# PSDT_RAM_v1_0_0.net
KiCad netlist of a schematic drawn in Altium Designer
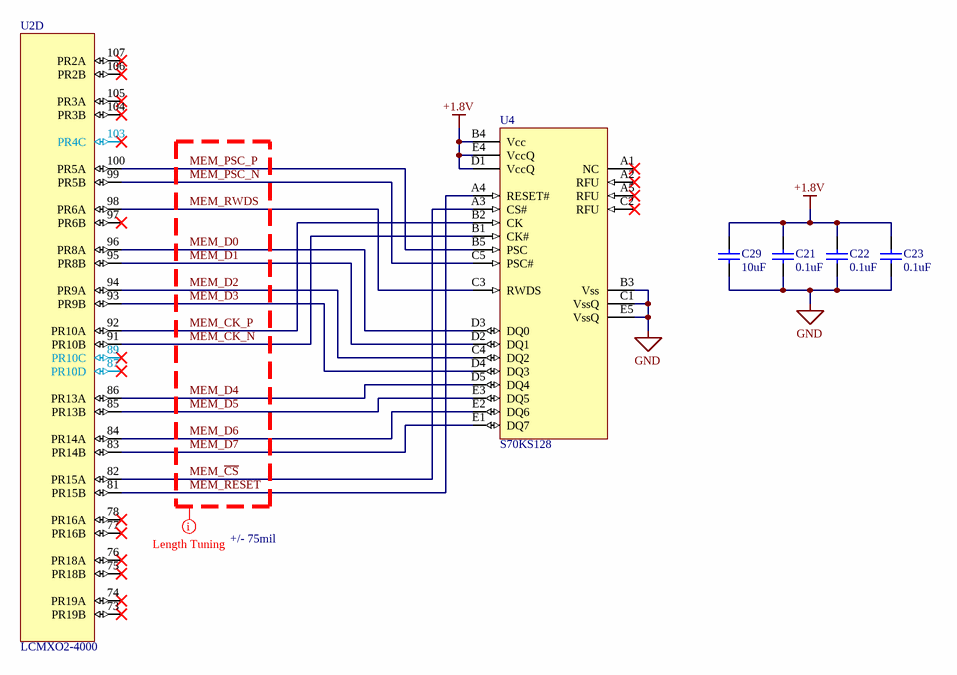
[diagram p0: PSDT RAM v1.0.0.SchDoc]

(export (version "E")
  (design (tool "Eeschema 10.0.6"))
  (components
    (comp (ref "C21")
      (value "0.1uF")
      (footprint "0402(1005)")
      (fields
        (field (name "MANF") "Samsung Electro-Mechanics")
        (field (name "TOLERANCE") "10")
        (field (name "VOLTAGE") "6.3")
        (field (name "MODIFIED BY") "jrowley")
        (field (name "APPROVED") "False")
      )
      (libsource (lib "MENG Database Library VPN") (part "Cap"))
    )
    (comp (ref "C22")
      (value "0.1uF")
      (footprint "0402(1005)")
      (fields
        (field (name "MANF") "Samsung Electro-Mechanics")
        (field (name "TOLERANCE") "10")
        (field (name "VOLTAGE") "6.3")
        (field (name "MODIFIED BY") "jrowley")
        (field (name "APPROVED") "False")
      )
      (libsource (lib "MENG Database Library VPN") (part "Cap"))
    )
    (comp (ref "C23")
      (value "0.1uF")
      (footprint "0402(1005)")
      (fields
        (field (name "MANF") "Samsung Electro-Mechanics")
        (field (name "TOLERANCE") "10")
        (field (name "VOLTAGE") "6.3")
        (field (name "MODIFIED BY") "jrowley")
        (field (name "APPROVED") "False")
      )
      (libsource (lib "MENG Database Library VPN") (part "Cap"))
    )
    (comp (ref "C29")
      (value "10uF")
      (footprint "0603(1608)")
      (fields
        (field (name "MANF") "Samsung Electro-Mechanics")
        (field (name "TOLERANCE") "20")
        (field (name "VOLTAGE") "25")
        (field (name "MODIFIED BY") "sotterbacher")
        (field (name "APPROVED") "True")
      )
      (libsource (lib "MENG Database Library VPN") (part "Cap"))
    )
    (comp (ref "U2")
      (value "LCMXO2-4000")
      (footprint "UL_TQFP144")
      (fields (field (name "MANF") "Lattice Semiconductor Corporation"))
      (libsource (lib "PS") (part "MachXO2-4000-TG144"))
    )
    (comp (ref "U4")
      (value "S70KS128")
      (footprint "Cypress-VAA024")
      (fields (field (name "MANF") "Cypress"))
      (libsource (lib "PS") (part "S70KS"))
    )
  )
  (nets
    (net (code "1") (name "+1.8V") (class "Default")
      (node (ref "C21") (pin "2") (pinfunction "2_2") (pintype "passive"))
      (node (ref "C22") (pin "2") (pinfunction "2_2") (pintype "passive"))
      (node (ref "C23") (pin "2") (pinfunction "2_2") (pintype "passive"))
      (node (ref "C29") (pin "2") (pinfunction "2_2") (pintype "passive"))
      (node (ref "U4") (pin "B4") (pinfunction "Vcc_B4") (pintype "power_in"))
      (node (ref "U4") (pin "D1") (pinfunction "VccQ_D1") (pintype "power_in"))
      (node (ref "U4") (pin "E4") (pinfunction "VccQ_E4") (pintype "power_in"))
    )
    (net (code "2") (name "/MEM_CK_N") (class "Default")
      (node (ref "U2") (pin "91") (pinfunction "PR10B_91") (pintype "bidirectional"))
      (node (ref "U4") (pin "B1") (pinfunction "CK#_B1") (pintype "input"))
    )
    (net (code "3") (name "/MEM_CK_P") (class "Default")
      (node (ref "U2") (pin "92") (pinfunction "PR10A_92") (pintype "bidirectional"))
      (node (ref "U4") (pin "B2") (pinfunction "CK_B2") (pintype "input"))
    )
    (net (code "4") (name "/MEM_D0") (class "Default")
      (node (ref "U2") (pin "96") (pinfunction "PR8A_96") (pintype "bidirectional"))
      (node (ref "U4") (pin "D3") (pinfunction "DQ0_D3") (pintype "bidirectional"))
    )
    (net (code "5") (name "/MEM_D1") (class "Default")
      (node (ref "U2") (pin "95") (pinfunction "PR8B_95") (pintype "bidirectional"))
      (node (ref "U4") (pin "D2") (pinfunction "DQ1_D2") (pintype "bidirectional"))
    )
    (net (code "6") (name "/MEM_D2") (class "Default")
      (node (ref "U2") (pin "94") (pinfunction "PR9A_94") (pintype "bidirectional"))
      (node (ref "U4") (pin "C4") (pinfunction "DQ2_C4") (pintype "bidirectional"))
    )
    (net (code "7") (name "/MEM_D3") (class "Default")
      (node (ref "U2") (pin "93") (pinfunction "PR9B_93") (pintype "bidirectional"))
      (node (ref "U4") (pin "D4") (pinfunction "DQ3_D4") (pintype "bidirectional"))
    )
    (net (code "8") (name "/MEM_D4") (class "Default")
      (node (ref "U2") (pin "86") (pinfunction "PR13A_86") (pintype "bidirectional"))
      (node (ref "U4") (pin "D5") (pinfunction "DQ4_D5") (pintype "bidirectional"))
    )
    (net (code "9") (name "/MEM_D5") (class "Default")
      (node (ref "U2") (pin "85") (pinfunction "PR13B_85") (pintype "bidirectional"))
      (node (ref "U4") (pin "E3") (pinfunction "DQ5_E3") (pintype "bidirectional"))
    )
    (net (code "10") (name "/MEM_D6") (class "Default")
      (node (ref "U2") (pin "84") (pinfunction "PR14A_84") (pintype "bidirectional"))
      (node (ref "U4") (pin "E2") (pinfunction "DQ6_E2") (pintype "bidirectional"))
    )
    (net (code "11") (name "/MEM_D7") (class "Default")
      (node (ref "U2") (pin "83") (pinfunction "PR14B_83") (pintype "bidirectional"))
      (node (ref "U4") (pin "E1") (pinfunction "DQ7_E1") (pintype "bidirectional"))
    )
    (net (code "12") (name "/MEM_PSC_N") (class "Default")
      (node (ref "U2") (pin "99") (pinfunction "PR5B_99") (pintype "bidirectional"))
      (node (ref "U4") (pin "C5") (pinfunction "PSC#_C5") (pintype "input"))
    )
    (net (code "13") (name "/MEM_PSC_P") (class "Default")
      (node (ref "U2") (pin "100") (pinfunction "PR5A_100") (pintype "bidirectional"))
      (node (ref "U4") (pin "B5") (pinfunction "PSC_B5") (pintype "input"))
    )
    (net (code "14") (name "/MEM_RWDS") (class "Default")
      (node (ref "U2") (pin "98") (pinfunction "PR6A_98") (pintype "bidirectional"))
      (node (ref "U4") (pin "C3") (pinfunction "RWDS_C3") (pintype "input"))
    )
    (net (code "15") (name "/MEM_~{CS}") (class "Default")
      (node (ref "U2") (pin "82") (pinfunction "PR15A_82") (pintype "bidirectional"))
      (node (ref "U4") (pin "A3") (pinfunction "CS#_A3") (pintype "input"))
    )
    (net (code "16") (name "/MEM_~{RESET}") (class "Default")
      (node (ref "U2") (pin "81") (pinfunction "PR15B_81") (pintype "bidirectional"))
      (node (ref "U4") (pin "A4") (pinfunction "RESET#_A4") (pintype "input"))
    )
    (net (code "17") (name "GND") (class "Default")
      (node (ref "C21") (pin "1") (pinfunction "1_1") (pintype "passive"))
      (node (ref "C22") (pin "1") (pinfunction "1_1") (pintype "passive"))
      (node (ref "C23") (pin "1") (pinfunction "1_1") (pintype "passive"))
      (node (ref "C29") (pin "1") (pinfunction "1_1") (pintype "passive"))
      (node (ref "U4") (pin "B3") (pinfunction "Vss_B3") (pintype "power_in"))
      (node (ref "U4") (pin "C1") (pinfunction "VssQ_C1") (pintype "power_in"))
      (node (ref "U4") (pin "E5") (pinfunction "VssQ_E5") (pintype "power_in"))
    )
    (net (code "18") (name "unconnected-(U2D-PR2A-Pad107)") (class "Default")
      (node (ref "U2") (pin "107") (pinfunction "PR2A_107") (pintype "bidirectional+no_connect"))
    )
    (net (code "19") (name "unconnected-(U2D-PR2B-Pad106)") (class "Default")
      (node (ref "U2") (pin "106") (pinfunction "PR2B_106") (pintype "bidirectional+no_connect"))
    )
    (net (code "20") (name "unconnected-(U2D-PR3A-Pad105)") (class "Default")
      (node (ref "U2") (pin "105") (pinfunction "PR3A_105") (pintype "bidirectional+no_connect"))
    )
    (net (code "21") (name "unconnected-(U2D-PR3B-Pad104)") (class "Default")
      (node (ref "U2") (pin "104") (pinfunction "PR3B_104") (pintype "bidirectional+no_connect"))
    )
    (net (code "22") (name "unconnected-(U2D-PR4C-Pad103)") (class "Default")
      (node (ref "U2") (pin "103") (pinfunction "PR4C_103") (pintype "bidirectional+no_connect"))
    )
    (net (code "23") (name "unconnected-(U2D-PR6B-Pad97)") (class "Default")
      (node (ref "U2") (pin "97") (pinfunction "PR6B_97") (pintype "bidirectional+no_connect"))
    )
    (net (code "24") (name "unconnected-(U2D-PR10C-Pad89)") (class "Default")
      (node (ref "U2") (pin "89") (pinfunction "PR10C_89") (pintype "bidirectional+no_connect"))
    )
    (net (code "25") (name "unconnected-(U2D-PR10D-Pad87)") (class "Default")
      (node (ref "U2") (pin "87") (pinfunction "PR10D_87") (pintype "bidirectional+no_connect"))
    )
    (net (code "26") (name "unconnected-(U2D-PR16A-Pad78)") (class "Default")
      (node (ref "U2") (pin "78") (pinfunction "PR16A_78") (pintype "bidirectional+no_connect"))
    )
    (net (code "27") (name "unconnected-(U2D-PR16B-Pad77)") (class "Default")
      (node (ref "U2") (pin "77") (pinfunction "PR16B_77") (pintype "bidirectional+no_connect"))
    )
    (net (code "28") (name "unconnected-(U2D-PR18A-Pad76)") (class "Default")
      (node (ref "U2") (pin "76") (pinfunction "PR18A_76") (pintype "bidirectional+no_connect"))
    )
    (net (code "29") (name "unconnected-(U2D-PR18B-Pad75)") (class "Default")
      (node (ref "U2") (pin "75") (pinfunction "PR18B_75") (pintype "bidirectional+no_connect"))
    )
    (net (code "30") (name "unconnected-(U2D-PR19A-Pad74)") (class "Default")
      (node (ref "U2") (pin "74") (pinfunction "PR19A_74") (pintype "bidirectional+no_connect"))
    )
    (net (code "31") (name "unconnected-(U2D-PR19B-Pad73)") (class "Default")
      (node (ref "U2") (pin "73") (pinfunction "PR19B_73") (pintype "bidirectional+no_connect"))
    )
    (net (code "32") (name "unconnected-(U4-NC-PadA1)") (class "Default")
      (node (ref "U4") (pin "A1") (pinfunction "NC_A1") (pintype "passive+no_connect"))
    )
    (net (code "33") (name "unconnected-(U4-RFU-PadA2)") (class "Default")
      (node (ref "U4") (pin "A2") (pinfunction "RFU_A2") (pintype "input+no_connect"))
    )
    (net (code "34") (name "unconnected-(U4-RFU-PadA5)") (class "Default")
      (node (ref "U4") (pin "A5") (pinfunction "RFU_A5") (pintype "input+no_connect"))
    )
    (net (code "35") (name "unconnected-(U4-RFU-PadC2)") (class "Default")
      (node (ref "U4") (pin "C2") (pinfunction "RFU_C2") (pintype "input+no_connect"))
    )
  )
)
